# amplificador_stereo.net
KiCad netlist of a schematic drawn in EAGLE
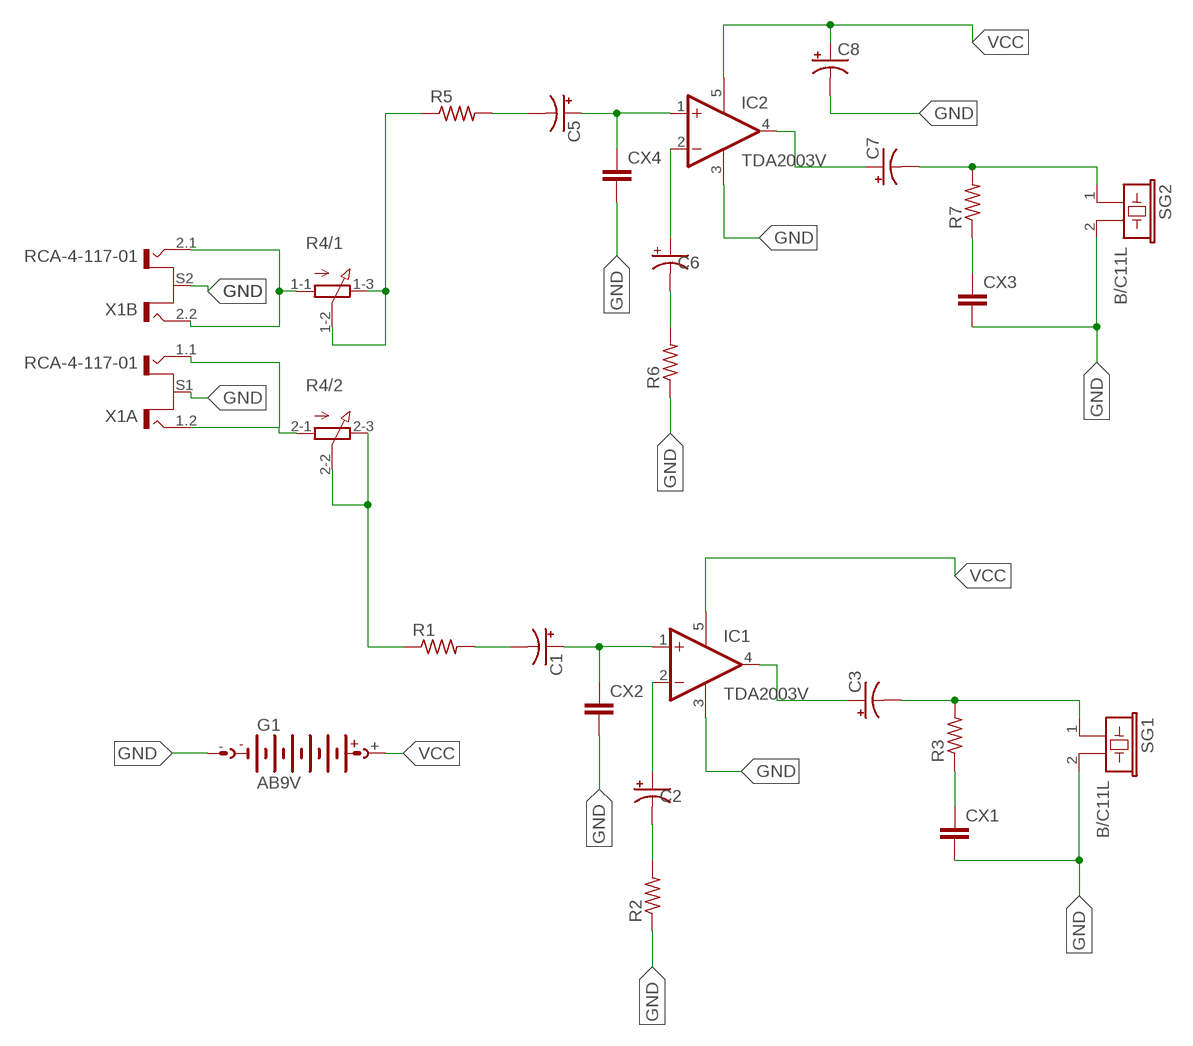
[diagram p0: schematic, sheet 1]

(export (version "E")
  (design (tool "Eeschema 10.0.6"))
  (components
    (comp (ref "C1")
      (value "CPOL-USB45181B")
      (footprint "eagle-import:B45181B")
      (libsource (lib "eagle-import") (part "CPOL-USB45181B"))
    )
    (comp (ref "C2")
      (value "CPOL-USB45181B")
      (footprint "eagle-import:B45181B")
      (libsource (lib "eagle-import") (part "CPOL-USB45181B"))
    )
    (comp (ref "C3")
      (value "CPOL-USB45181B")
      (footprint "eagle-import:B45181B")
      (libsource (lib "eagle-import") (part "CPOL-USB45181B"))
    )
    (comp (ref "C5")
      (value "CPOL-USB45181B")
      (footprint "eagle-import:B45181B")
      (libsource (lib "eagle-import") (part "CPOL-USB45181B"))
    )
    (comp (ref "C6")
      (value "CPOL-USB45181B")
      (footprint "eagle-import:B45181B")
      (libsource (lib "eagle-import") (part "CPOL-USB45181B"))
    )
    (comp (ref "C7")
      (value "CPOL-USB45181B")
      (footprint "eagle-import:B45181B")
      (libsource (lib "eagle-import") (part "CPOL-USB45181B"))
    )
    (comp (ref "C8")
      (value "CPOL-USB45181B")
      (footprint "eagle-import:B45181B")
      (libsource (lib "eagle-import") (part "CPOL-USB45181B"))
    )
    (comp (ref "CX1")
      (value "CXXC10B6")
      (footprint "eagle-import:XC10B6")
      (libsource (lib "eagle-import") (part "CXXC10B6"))
    )
    (comp (ref "CX2")
      (value "CXXC10B6")
      (footprint "eagle-import:XC10B6")
      (libsource (lib "eagle-import") (part "CXXC10B6"))
    )
    (comp (ref "CX3")
      (value "CXXC10B6")
      (footprint "eagle-import:XC10B6")
      (libsource (lib "eagle-import") (part "CXXC10B6"))
    )
    (comp (ref "CX4")
      (value "CXXC10B6")
      (footprint "eagle-import:XC10B6")
      (libsource (lib "eagle-import") (part "CXXC10B6"))
    )
    (comp (ref "G1")
      (value "AB9V")
      (footprint "eagle-import:AB9V")
      (libsource (lib "eagle-import") (part "AB9V"))
    )
    (comp (ref "IC1")
      (value "TDA2003V")
      (footprint "eagle-import:CB360")
      (libsource (lib "eagle-import") (part "TDA2003V"))
    )
    (comp (ref "IC2")
      (value "TDA2003V")
      (footprint "eagle-import:CB360")
      (libsource (lib "eagle-import") (part "TDA2003V"))
    )
    (comp (ref "R1")
      (value "R-US_0204/7")
      (footprint "eagle-import:0204_7")
      (libsource (lib "eagle-import") (part "R-US_0204/7"))
    )
    (comp (ref "R2")
      (value "R-US_0204/7")
      (footprint "eagle-import:0204_7")
      (libsource (lib "eagle-import") (part "R-US_0204/7"))
    )
    (comp (ref "R3")
      (value "R-US_0204/7")
      (footprint "eagle-import:0204_7")
      (libsource (lib "eagle-import") (part "R-US_0204/7"))
    )
    (comp (ref "R4")
      (value "3RP/1610G")
      (footprint "eagle-import:3RP_1610G")
      (libsource (lib "eagle-import") (part "3RP/1610G"))
    )
    (comp (ref "R5")
      (value "R-US_0204/7")
      (footprint "eagle-import:0204_7")
      (libsource (lib "eagle-import") (part "R-US_0204/7"))
    )
    (comp (ref "R6")
      (value "R-US_0204/7")
      (footprint "eagle-import:0204_7")
      (libsource (lib "eagle-import") (part "R-US_0204/7"))
    )
    (comp (ref "R7")
      (value "R-US_0204/7")
      (footprint "eagle-import:0204_7")
      (libsource (lib "eagle-import") (part "R-US_0204/7"))
    )
    (comp (ref "SG1")
      (value "B/C11L")
      (footprint "eagle-import:B_C11L")
      (libsource (lib "eagle-import") (part "B/C11L"))
    )
    (comp (ref "SG2")
      (value "B/C11L")
      (footprint "eagle-import:B_C11L")
      (libsource (lib "eagle-import") (part "B/C11L"))
    )
    (comp (ref "X1")
      (value "RCA-4-117-01")
      (footprint "eagle-import:RCA-4-117-01")
      (libsource (lib "eagle-import") (part "RCA-4-117-01"))
    )
  )
  (nets
    (net (code "1") (name "GND") (class "Default")
      (node (ref "C8") (pin "-") (pinfunction "-_-") (pintype "passive"))
      (node (ref "CX1") (pin "2") (pinfunction "2_2") (pintype "passive"))
      (node (ref "CX2") (pin "2") (pinfunction "2_2") (pintype "passive"))
      (node (ref "CX3") (pin "2") (pinfunction "2_2") (pintype "passive"))
      (node (ref "CX4") (pin "2") (pinfunction "2_2") (pintype "passive"))
      (node (ref "G1") (pin "-") (pinfunction "-_-") (pintype "passive"))
      (node (ref "IC1") (pin "3") (pinfunction "GND_3") (pintype "power_in"))
      (node (ref "IC2") (pin "3") (pinfunction "GND_3") (pintype "power_in"))
      (node (ref "R2") (pin "1") (pinfunction "1_1") (pintype "passive"))
      (node (ref "R6") (pin "1") (pinfunction "1_1") (pintype "passive"))
      (node (ref "SG1") (pin "2") (pinfunction "2_2") (pintype "passive"))
      (node (ref "SG2") (pin "2") (pinfunction "2_2") (pintype "passive"))
      (node (ref "X1") (pin "S1") (pinfunction "S_S1") (pintype "passive"))
      (node (ref "X1") (pin "S2") (pinfunction "S_S2") (pintype "passive"))
    )
    (net (code "2") (name "Net-(C1-Pad-)") (class "Default")
      (node (ref "C1") (pin "-") (pinfunction "-_-") (pintype "passive"))
      (node (ref "R1") (pin "2") (pinfunction "2_2") (pintype "passive"))
    )
    (net (code "3") (name "Net-(C2-Pad-)") (class "Default")
      (node (ref "C2") (pin "-") (pinfunction "-_-") (pintype "passive"))
      (node (ref "R2") (pin "2") (pinfunction "2_2") (pintype "passive"))
    )
    (net (code "4") (name "Net-(C3-Pad-)") (class "Default")
      (node (ref "C3") (pin "-") (pinfunction "-_-") (pintype "passive"))
      (node (ref "R3") (pin "2") (pinfunction "2_2") (pintype "passive"))
      (node (ref "SG1") (pin "1") (pinfunction "1_1") (pintype "passive"))
    )
    (net (code "5") (name "Net-(C5-Pad-)") (class "Default")
      (node (ref "C5") (pin "-") (pinfunction "-_-") (pintype "passive"))
      (node (ref "R5") (pin "2") (pinfunction "2_2") (pintype "passive"))
    )
    (net (code "6") (name "Net-(C6-Pad-)") (class "Default")
      (node (ref "C6") (pin "-") (pinfunction "-_-") (pintype "passive"))
      (node (ref "R6") (pin "2") (pinfunction "2_2") (pintype "passive"))
    )
    (net (code "7") (name "Net-(C7-Pad-)") (class "Default")
      (node (ref "C7") (pin "-") (pinfunction "-_-") (pintype "passive"))
      (node (ref "R7") (pin "2") (pinfunction "2_2") (pintype "passive"))
      (node (ref "SG2") (pin "1") (pinfunction "1_1") (pintype "passive"))
    )
    (net (code "8") (name "Net-(CX1-Pad1)") (class "Default")
      (node (ref "CX1") (pin "1") (pinfunction "1_1") (pintype "passive"))
      (node (ref "R3") (pin "1") (pinfunction "1_1") (pintype "passive"))
    )
    (net (code "9") (name "Net-(CX3-Pad1)") (class "Default")
      (node (ref "CX3") (pin "1") (pinfunction "1_1") (pintype "passive"))
      (node (ref "R7") (pin "1") (pinfunction "1_1") (pintype "passive"))
    )
    (net (code "10") (name "Net-(IC1-+IN)") (class "Default")
      (node (ref "C1") (pin "+") (pinfunction "+_+") (pintype "passive"))
      (node (ref "CX2") (pin "1") (pinfunction "1_1") (pintype "passive"))
      (node (ref "IC1") (pin "1") (pinfunction "+IN_1") (pintype "input"))
    )
    (net (code "11") (name "Net-(IC1--IN)") (class "Default")
      (node (ref "C2") (pin "+") (pinfunction "+_+") (pintype "passive"))
      (node (ref "IC1") (pin "2") (pinfunction "-IN_2") (pintype "input"))
    )
    (net (code "12") (name "Net-(IC1-OUT)") (class "Default")
      (node (ref "C3") (pin "+") (pinfunction "+_+") (pintype "passive"))
      (node (ref "IC1") (pin "4") (pinfunction "OUT_4") (pintype "output"))
    )
    (net (code "13") (name "Net-(IC2-+IN)") (class "Default")
      (node (ref "C5") (pin "+") (pinfunction "+_+") (pintype "passive"))
      (node (ref "CX4") (pin "1") (pinfunction "1_1") (pintype "passive"))
      (node (ref "IC2") (pin "1") (pinfunction "+IN_1") (pintype "input"))
    )
    (net (code "14") (name "Net-(IC2--IN)") (class "Default")
      (node (ref "C6") (pin "+") (pinfunction "+_+") (pintype "passive"))
      (node (ref "IC2") (pin "2") (pinfunction "-IN_2") (pintype "input"))
    )
    (net (code "15") (name "Net-(IC2-OUT)") (class "Default")
      (node (ref "C7") (pin "+") (pinfunction "+_+") (pintype "passive"))
      (node (ref "IC2") (pin "4") (pinfunction "OUT_4") (pintype "output"))
    )
    (net (code "16") (name "Net-(R4A-A)") (class "Default")
      (node (ref "R4") (pin "1-1") (pinfunction "A_1-1") (pintype "passive"))
      (node (ref "X1") (pin "2.1") (pinfunction "T1_2.1") (pintype "passive"))
      (node (ref "X1") (pin "2.2") (pinfunction "T2_2.2") (pintype "passive"))
    )
    (net (code "17") (name "Net-(R4A-E)") (class "Default")
      (node (ref "R4") (pin "1-2") (pinfunction "S_1-2") (pintype "passive"))
      (node (ref "R4") (pin "1-3") (pinfunction "E_1-3") (pintype "passive"))
      (node (ref "R5") (pin "1") (pinfunction "1_1") (pintype "passive"))
    )
    (net (code "18") (name "Net-(R4B-A)") (class "Default")
      (node (ref "R4") (pin "2-1") (pinfunction "A_2-1") (pintype "passive"))
      (node (ref "X1") (pin "1.1") (pinfunction "T1_1.1") (pintype "passive"))
      (node (ref "X1") (pin "1.2") (pinfunction "T2_1.2") (pintype "passive"))
    )
    (net (code "19") (name "Net-(R4B-E)") (class "Default")
      (node (ref "R1") (pin "1") (pinfunction "1_1") (pintype "passive"))
      (node (ref "R4") (pin "2-2") (pinfunction "S_2-2") (pintype "passive"))
      (node (ref "R4") (pin "2-3") (pinfunction "E_2-3") (pintype "passive"))
    )
    (net (code "20") (name "VCC") (class "Default")
      (node (ref "C8") (pin "+") (pinfunction "+_+") (pintype "passive"))
      (node (ref "G1") (pin "+") (pinfunction "+_+") (pintype "passive"))
      (node (ref "IC1") (pin "5") (pinfunction "V+_5") (pintype "power_in"))
      (node (ref "IC2") (pin "5") (pinfunction "V+_5") (pintype "power_in"))
    )
  )
)
